# PCM2707C_HeadPhone_V2.net
KiCad netlist of a schematic drawn in EAGLE
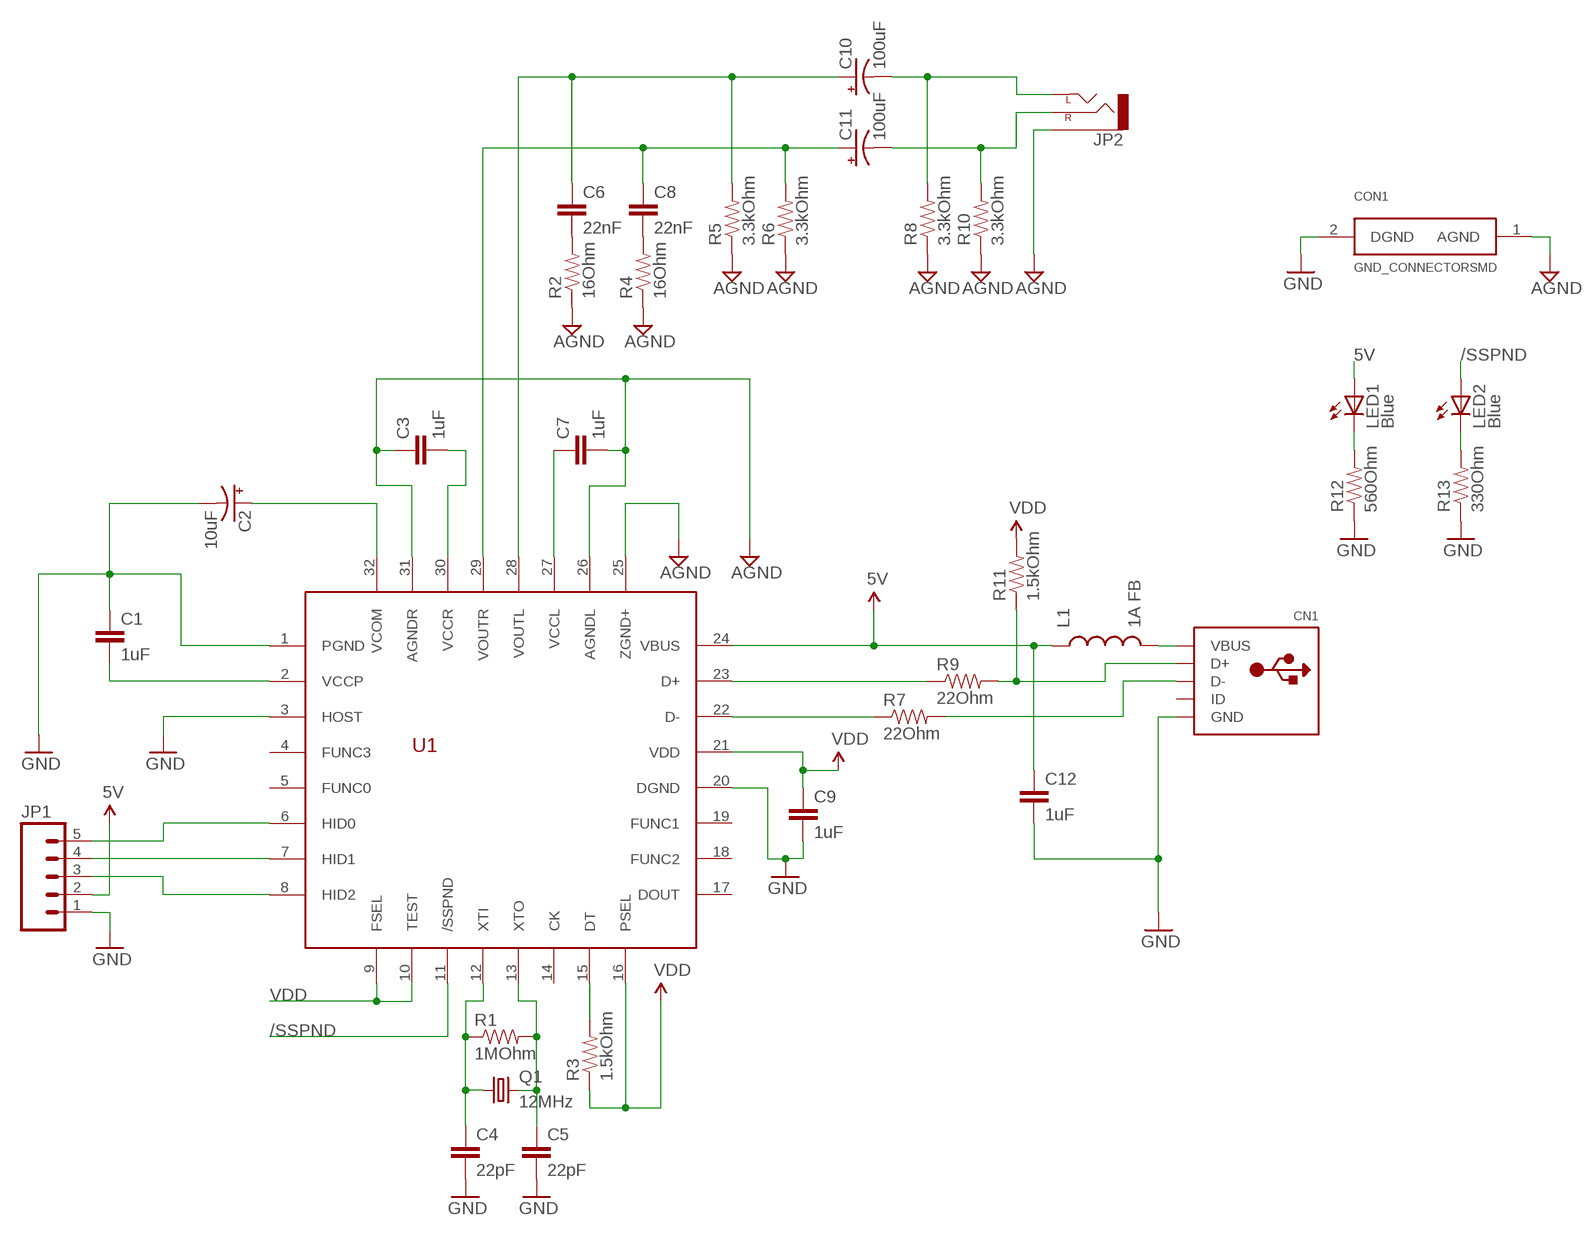
[diagram p0: schematic, sheet 1]

(export (version "E")
  (design (tool "Eeschema 10.0.6"))
  (components
    (comp (ref "C1")
      (value "1uF")
      (footprint "eagle-import:0805")
      (libsource (lib "eagle-import") (part "CAP0805"))
    )
    (comp (ref "C2")
      (value "10uF")
      (footprint "eagle-import:PANASONIC_C")
      (libsource (lib "eagle-import") (part "CAP_POLC"))
    )
    (comp (ref "C3")
      (value "1uF")
      (footprint "eagle-import:0805")
      (libsource (lib "eagle-import") (part "CAP0805"))
    )
    (comp (ref "C4")
      (value "22pF")
      (footprint "eagle-import:0805")
      (libsource (lib "eagle-import") (part "CAP0805"))
    )
    (comp (ref "C5")
      (value "22pF")
      (footprint "eagle-import:0805")
      (libsource (lib "eagle-import") (part "CAP0805"))
    )
    (comp (ref "C6")
      (value "22nF")
      (footprint "eagle-import:1210")
      (libsource (lib "eagle-import") (part "CAP1210"))
    )
    (comp (ref "C7")
      (value "1uF")
      (footprint "eagle-import:0805")
      (libsource (lib "eagle-import") (part "CAP0805"))
    )
    (comp (ref "C8")
      (value "22nF")
      (footprint "eagle-import:1210")
      (libsource (lib "eagle-import") (part "CAP1210"))
    )
    (comp (ref "C9")
      (value "1uF")
      (footprint "eagle-import:0805")
      (libsource (lib "eagle-import") (part "CAP0805"))
    )
    (comp (ref "C10")
      (value "100uF")
      (footprint "eagle-import:PANASONIC_D")
      (libsource (lib "eagle-import") (part "CAP_POLD"))
    )
    (comp (ref "C11")
      (value "100uF")
      (footprint "eagle-import:PANASONIC_D")
      (libsource (lib "eagle-import") (part "CAP_POLD"))
    )
    (comp (ref "C12")
      (value "1uF")
      (footprint "eagle-import:0805")
      (libsource (lib "eagle-import") (part "CAP0805"))
    )
    (comp (ref "CN1")
      (value "USBMINIB")
      (footprint "eagle-import:USB-MINIB")
      (libsource (lib "eagle-import") (part "USBMINIB"))
    )
    (comp (ref "CON1")
      (value "GND_CONNECTORSMD")
      (footprint "eagle-import:GND_CONNECTOR")
      (libsource (lib "eagle-import") (part "GND_CONNECTORSMD"))
    )
    (comp (ref "JP1")
      (value "M05LOCK")
      (footprint "eagle-import:1X05_LOCK")
      (libsource (lib "eagle-import") (part "M05LOCK"))
    )
    (comp (ref "JP2")
      (value "AUDIO-JACKPTH")
      (footprint "eagle-import:AUDIO-JACK")
      (libsource (lib "eagle-import") (part "AUDIO-JACKPTH"))
    )
    (comp (ref "L1")
      (value "1A FB")
      (footprint "eagle-import:0805")
      (libsource (lib "eagle-import") (part "INDUCTOR0805"))
    )
    (comp (ref "LED1")
      (value "Blue")
      (footprint "eagle-import:LED-0603")
      (libsource (lib "eagle-import") (part "LED0603"))
    )
    (comp (ref "LED2")
      (value "Blue")
      (footprint "eagle-import:LED-0603")
      (libsource (lib "eagle-import") (part "LED0603"))
    )
    (comp (ref "Q1")
      (value "12MHz")
      (footprint "eagle-import:HC49U-V")
      (libsource (lib "eagle-import") (part "CRYSTALHC49U-V"))
    )
    (comp (ref "R1")
      (value "1MOhm")
      (footprint "eagle-import:0805")
      (libsource (lib "eagle-import") (part "RESISTOR0805-RES"))
    )
    (comp (ref "R2")
      (value "16Ohm")
      (footprint "eagle-import:0805")
      (libsource (lib "eagle-import") (part "RESISTOR0805-RES"))
    )
    (comp (ref "R3")
      (value "1.5kOhm")
      (footprint "eagle-import:0805")
      (libsource (lib "eagle-import") (part "RESISTOR0805-RES"))
    )
    (comp (ref "R4")
      (value "16Ohm")
      (footprint "eagle-import:0805")
      (libsource (lib "eagle-import") (part "RESISTOR0805-RES"))
    )
    (comp (ref "R5")
      (value "3.3kOhm")
      (footprint "eagle-import:0805")
      (libsource (lib "eagle-import") (part "RESISTOR0805-RES"))
    )
    (comp (ref "R6")
      (value "3.3kOhm")
      (footprint "eagle-import:0805")
      (libsource (lib "eagle-import") (part "RESISTOR0805-RES"))
    )
    (comp (ref "R7")
      (value "22Ohm")
      (footprint "eagle-import:0805")
      (libsource (lib "eagle-import") (part "RESISTOR0805-RES"))
    )
    (comp (ref "R8")
      (value "3.3kOhm")
      (footprint "eagle-import:0805")
      (libsource (lib "eagle-import") (part "RESISTOR0805-RES"))
    )
    (comp (ref "R9")
      (value "22Ohm")
      (footprint "eagle-import:0805")
      (libsource (lib "eagle-import") (part "RESISTOR0805-RES"))
    )
    (comp (ref "R10")
      (value "3.3kOhm")
      (footprint "eagle-import:0805")
      (libsource (lib "eagle-import") (part "RESISTOR0805-RES"))
    )
    (comp (ref "R11")
      (value "1.5kOhm")
      (footprint "eagle-import:0805")
      (libsource (lib "eagle-import") (part "RESISTOR0805-RES"))
    )
    (comp (ref "R12")
      (value "560Ohm")
      (footprint "eagle-import:0805")
      (libsource (lib "eagle-import") (part "RESISTOR0805-RES"))
    )
    (comp (ref "R13")
      (value "330Ohm")
      (footprint "eagle-import:0805")
      (libsource (lib "eagle-import") (part "RESISTOR0805-RES"))
    )
    (comp (ref "U1")
      (value "PCM2707C_TQFP32\"")
      (footprint "eagle-import:32TQFP_PCM2707C")
      (libsource (lib "eagle-import") (part "PCM2707C_TQFP32{dblquote}"))
    )
  )
  (nets
    (net (code "1") (name "/{slash}SSPND") (class "Default")
      (node (ref "LED2") (pin "A") (pinfunction "A_A") (pintype "passive"))
      (node (ref "U1") (pin "11") (pinfunction "/SSPND_11") (pintype "bidirectional"))
    )
    (net (code "2") (name "5V") (class "Default")
      (node (ref "C12") (pin "1") (pinfunction "1_1") (pintype "passive"))
      (node (ref "JP1") (pin "2") (pinfunction "2_2") (pintype "passive"))
      (node (ref "L1") (pin "1") (pinfunction "1_1") (pintype "passive"))
      (node (ref "LED1") (pin "A") (pinfunction "A_A") (pintype "passive"))
      (node (ref "U1") (pin "24") (pinfunction "VBUS_24") (pintype "bidirectional"))
    )
    (net (code "3") (name "AGND") (class "Default")
      (node (ref "C3") (pin "1") (pinfunction "1_1") (pintype "passive"))
      (node (ref "C7") (pin "2") (pinfunction "2_2") (pintype "passive"))
      (node (ref "CON1") (pin "1") (pinfunction "AGND_1") (pintype "bidirectional"))
      (node (ref "JP2") (pin "SLEEVE") (pinfunction "SLEEVE_SLEEVE") (pintype "bidirectional"))
      (node (ref "R10") (pin "1") (pinfunction "1_1") (pintype "passive"))
      (node (ref "R2") (pin "1") (pinfunction "1_1") (pintype "passive"))
      (node (ref "R4") (pin "1") (pinfunction "1_1") (pintype "passive"))
      (node (ref "R5") (pin "1") (pinfunction "1_1") (pintype "passive"))
      (node (ref "R6") (pin "1") (pinfunction "1_1") (pintype "passive"))
      (node (ref "R8") (pin "1") (pinfunction "1_1") (pintype "passive"))
      (node (ref "U1") (pin "25") (pinfunction "ZGND+_25") (pintype "bidirectional"))
      (node (ref "U1") (pin "26") (pinfunction "AGNDL_26") (pintype "bidirectional"))
      (node (ref "U1") (pin "31") (pinfunction "AGNDR_31") (pintype "bidirectional"))
    )
    (net (code "4") (name "GND") (class "Default")
      (node (ref "C1") (pin "1") (pinfunction "1_1") (pintype "passive"))
      (node (ref "C12") (pin "2") (pinfunction "2_2") (pintype "passive"))
      (node (ref "C2") (pin "-") (pinfunction "-_-") (pintype "passive"))
      (node (ref "C4") (pin "2") (pinfunction "2_2") (pintype "passive"))
      (node (ref "C5") (pin "2") (pinfunction "2_2") (pintype "passive"))
      (node (ref "C9") (pin "2") (pinfunction "2_2") (pintype "passive"))
      (node (ref "CN1") (pin "GND") (pinfunction "GND_GND") (pintype "power_in"))
      (node (ref "CON1") (pin "2") (pinfunction "DGND_2") (pintype "bidirectional"))
      (node (ref "JP1") (pin "1") (pinfunction "1_1") (pintype "passive"))
      (node (ref "R12") (pin "1") (pinfunction "1_1") (pintype "passive"))
      (node (ref "R13") (pin "1") (pinfunction "1_1") (pintype "passive"))
      (node (ref "U1") (pin "1") (pinfunction "PGND_1") (pintype "bidirectional"))
      (node (ref "U1") (pin "20") (pinfunction "DGND_20") (pintype "bidirectional"))
      (node (ref "U1") (pin "3") (pinfunction "HOST_3") (pintype "bidirectional"))
    )
    (net (code "5") (name "Net-(C6-Pad2)") (class "Default")
      (node (ref "C6") (pin "2") (pinfunction "2_2") (pintype "passive"))
      (node (ref "R2") (pin "2") (pinfunction "2_2") (pintype "passive"))
    )
    (net (code "6") (name "Net-(C8-Pad2)") (class "Default")
      (node (ref "C8") (pin "2") (pinfunction "2_2") (pintype "passive"))
      (node (ref "R4") (pin "2") (pinfunction "2_2") (pintype "passive"))
    )
    (net (code "7") (name "Net-(CN1-PadD+)") (class "Default")
      (node (ref "CN1") (pin "D+") (pinfunction "D+_D+") (pintype "bidirectional"))
      (node (ref "R11") (pin "1") (pinfunction "1_1") (pintype "passive"))
      (node (ref "R9") (pin "2") (pinfunction "2_2") (pintype "passive"))
    )
    (net (code "8") (name "Net-(CN1-PadD-)") (class "Default")
      (node (ref "CN1") (pin "D-") (pinfunction "D-_D-") (pintype "bidirectional"))
      (node (ref "R7") (pin "2") (pinfunction "2_2") (pintype "passive"))
    )
    (net (code "9") (name "Net-(CN1-PadVBUS)") (class "Default")
      (node (ref "CN1") (pin "VBUS") (pinfunction "VBUS_VBUS") (pintype "power_in"))
      (node (ref "L1") (pin "2") (pinfunction "2_2") (pintype "passive"))
    )
    (net (code "10") (name "Net-(JP2-LEFT)") (class "Default")
      (node (ref "C10") (pin "-") (pinfunction "-_-") (pintype "passive"))
      (node (ref "JP2") (pin "TIP") (pinfunction "LEFT_TIP") (pintype "bidirectional"))
      (node (ref "R8") (pin "2") (pinfunction "2_2") (pintype "passive"))
    )
    (net (code "11") (name "Net-(JP2-RIGHT)") (class "Default")
      (node (ref "C11") (pin "-") (pinfunction "-_-") (pintype "passive"))
      (node (ref "JP2") (pin "RING") (pinfunction "RIGHT_RING") (pintype "bidirectional"))
      (node (ref "R10") (pin "2") (pinfunction "2_2") (pintype "passive"))
    )
    (net (code "12") (name "Net-(LED1-PadC)") (class "Default")
      (node (ref "LED1") (pin "C") (pinfunction "C_C") (pintype "passive"))
      (node (ref "R12") (pin "2") (pinfunction "2_2") (pintype "passive"))
    )
    (net (code "13") (name "Net-(LED2-PadC)") (class "Default")
      (node (ref "LED2") (pin "C") (pinfunction "C_C") (pintype "passive"))
      (node (ref "R13") (pin "2") (pinfunction "2_2") (pintype "passive"))
    )
    (net (code "14") (name "Net-(U1-D+)") (class "Default")
      (node (ref "R9") (pin "1") (pinfunction "1_1") (pintype "passive"))
      (node (ref "U1") (pin "23") (pinfunction "D+_23") (pintype "bidirectional"))
    )
    (net (code "15") (name "Net-(U1-D-)") (class "Default")
      (node (ref "R7") (pin "1") (pinfunction "1_1") (pintype "passive"))
      (node (ref "U1") (pin "22") (pinfunction "D-_22") (pintype "bidirectional"))
    )
    (net (code "16") (name "Net-(U1-DT)") (class "Default")
      (node (ref "R3") (pin "2") (pinfunction "2_2") (pintype "passive"))
      (node (ref "U1") (pin "15") (pinfunction "DT_15") (pintype "bidirectional"))
    )
    (net (code "17") (name "Net-(U1-HID0)") (class "Default")
      (node (ref "JP1") (pin "5") (pinfunction "5_5") (pintype "passive"))
      (node (ref "U1") (pin "6") (pinfunction "HID0_6") (pintype "bidirectional"))
    )
    (net (code "18") (name "Net-(U1-HID1)") (class "Default")
      (node (ref "JP1") (pin "4") (pinfunction "4_4") (pintype "passive"))
      (node (ref "U1") (pin "7") (pinfunction "HID1_7") (pintype "bidirectional"))
    )
    (net (code "19") (name "Net-(U1-HID2)") (class "Default")
      (node (ref "JP1") (pin "3") (pinfunction "3_3") (pintype "passive"))
      (node (ref "U1") (pin "8") (pinfunction "HID2_8") (pintype "bidirectional"))
    )
    (net (code "20") (name "Net-(U1-VCCL)") (class "Default")
      (node (ref "C7") (pin "1") (pinfunction "1_1") (pintype "passive"))
      (node (ref "U1") (pin "27") (pinfunction "VCCL_27") (pintype "bidirectional"))
    )
    (net (code "21") (name "Net-(U1-VCCP)") (class "Default")
      (node (ref "C1") (pin "2") (pinfunction "2_2") (pintype "passive"))
      (node (ref "U1") (pin "2") (pinfunction "VCCP_2") (pintype "bidirectional"))
    )
    (net (code "22") (name "Net-(U1-VCCR)") (class "Default")
      (node (ref "C3") (pin "2") (pinfunction "2_2") (pintype "passive"))
      (node (ref "U1") (pin "30") (pinfunction "VCCR_30") (pintype "bidirectional"))
    )
    (net (code "23") (name "Net-(U1-VCOM)") (class "Default")
      (node (ref "C2") (pin "+") (pinfunction "+_+") (pintype "passive"))
      (node (ref "U1") (pin "32") (pinfunction "VCOM_32") (pintype "bidirectional"))
    )
    (net (code "24") (name "Net-(U1-VOUTL)") (class "Default")
      (node (ref "C10") (pin "+") (pinfunction "+_+") (pintype "passive"))
      (node (ref "C6") (pin "1") (pinfunction "1_1") (pintype "passive"))
      (node (ref "R5") (pin "2") (pinfunction "2_2") (pintype "passive"))
      (node (ref "U1") (pin "28") (pinfunction "VOUTL_28") (pintype "bidirectional"))
    )
    (net (code "25") (name "Net-(U1-VOUTR)") (class "Default")
      (node (ref "C11") (pin "+") (pinfunction "+_+") (pintype "passive"))
      (node (ref "C8") (pin "1") (pinfunction "1_1") (pintype "passive"))
      (node (ref "R6") (pin "2") (pinfunction "2_2") (pintype "passive"))
      (node (ref "U1") (pin "29") (pinfunction "VOUTR_29") (pintype "bidirectional"))
    )
    (net (code "26") (name "Net-(U1-XTI)") (class "Default")
      (node (ref "C4") (pin "1") (pinfunction "1_1") (pintype "passive"))
      (node (ref "Q1") (pin "1") (pinfunction "1_1") (pintype "passive"))
      (node (ref "R1") (pin "1") (pinfunction "1_1") (pintype "passive"))
      (node (ref "U1") (pin "12") (pinfunction "XTI_12") (pintype "bidirectional"))
    )
    (net (code "27") (name "Net-(U1-XTO)") (class "Default")
      (node (ref "C5") (pin "1") (pinfunction "1_1") (pintype "passive"))
      (node (ref "Q1") (pin "2") (pinfunction "2_2") (pintype "passive"))
      (node (ref "R1") (pin "2") (pinfunction "2_2") (pintype "passive"))
      (node (ref "U1") (pin "13") (pinfunction "XTO_13") (pintype "bidirectional"))
    )
    (net (code "28") (name "VDD") (class "Default")
      (node (ref "C9") (pin "1") (pinfunction "1_1") (pintype "passive"))
      (node (ref "R11") (pin "2") (pinfunction "2_2") (pintype "passive"))
      (node (ref "R3") (pin "1") (pinfunction "1_1") (pintype "passive"))
      (node (ref "U1") (pin "10") (pinfunction "TEST_10") (pintype "bidirectional"))
      (node (ref "U1") (pin "16") (pinfunction "PSEL_16") (pintype "bidirectional"))
      (node (ref "U1") (pin "21") (pinfunction "VDD_21") (pintype "bidirectional"))
      (node (ref "U1") (pin "9") (pinfunction "FSEL_9") (pintype "bidirectional"))
    )
    (net (code "29") (name "unconnected-(CN1-PadID)") (class "Default")
      (node (ref "CN1") (pin "ID") (pinfunction "ID_ID") (pintype "bidirectional"))
    )
    (net (code "30") (name "unconnected-(U1-CK-Pad14)") (class "Default")
      (node (ref "U1") (pin "14") (pinfunction "CK_14") (pintype "bidirectional"))
    )
    (net (code "31") (name "unconnected-(U1-DOUT-Pad17)") (class "Default")
      (node (ref "U1") (pin "17") (pinfunction "DOUT_17") (pintype "bidirectional"))
    )
    (net (code "32") (name "unconnected-(U1-FUNC0-Pad5)") (class "Default")
      (node (ref "U1") (pin "5") (pinfunction "FUNC0_5") (pintype "bidirectional"))
    )
    (net (code "33") (name "unconnected-(U1-FUNC1-Pad19)") (class "Default")
      (node (ref "U1") (pin "19") (pinfunction "FUNC1_19") (pintype "bidirectional"))
    )
    (net (code "34") (name "unconnected-(U1-FUNC2-Pad18)") (class "Default")
      (node (ref "U1") (pin "18") (pinfunction "FUNC2_18") (pintype "bidirectional"))
    )
    (net (code "35") (name "unconnected-(U1-FUNC3-Pad4)") (class "Default")
      (node (ref "U1") (pin "4") (pinfunction "FUNC3_4") (pintype "bidirectional"))
    )
  )
)
